# control-board-v1-fix.net
KiCad netlist of a schematic drawn in EAGLE
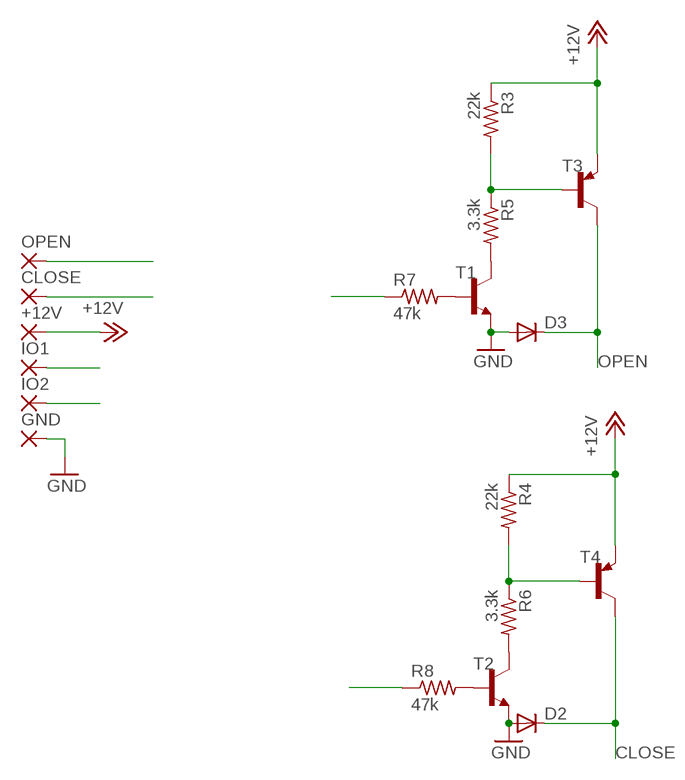
[diagram p0: schematic, sheet 1]

(export (version "E")
  (design (tool "Eeschema 10.0.6"))
  (components
    (comp (ref "+12V")
      (value "1,6/0,8")
      (footprint "eagle-import:1,6_0,8")
      (libsource (lib "eagle-import") (part "1,6/0,8"))
    )
    (comp (ref "CLOSE")
      (value "1,6/0,8")
      (footprint "eagle-import:1,6_0,8")
      (libsource (lib "eagle-import") (part "1,6/0,8"))
    )
    (comp (ref "D2")
      (value "DIODE-MICROMELF-W")
      (footprint "eagle-import:MICROMELF-W")
      (libsource (lib "eagle-import") (part "DIODE-MICROMELF-W"))
    )
    (comp (ref "D3")
      (value "DIODE-MICROMELF-W")
      (footprint "eagle-import:MICROMELF-W")
      (libsource (lib "eagle-import") (part "DIODE-MICROMELF-W"))
    )
    (comp (ref "GND")
      (value "1,6/0,8")
      (footprint "eagle-import:1,6_0,8")
      (libsource (lib "eagle-import") (part "1,6/0,8"))
    )
    (comp (ref "IO1")
      (value "1,6/0,8")
      (footprint "eagle-import:1,6_0,8")
      (libsource (lib "eagle-import") (part "1,6/0,8"))
    )
    (comp (ref "IO2")
      (value "1,6/0,8")
      (footprint "eagle-import:1,6_0,8")
      (libsource (lib "eagle-import") (part "1,6/0,8"))
    )
    (comp (ref "OPEN")
      (value "1,6/0,8")
      (footprint "eagle-import:1,6_0,8")
      (libsource (lib "eagle-import") (part "1,6/0,8"))
    )
    (comp (ref "R3")
      (value "22k")
      (footprint "eagle-import:R0603")
      (libsource (lib "eagle-import") (part "R-US_R0603"))
    )
    (comp (ref "R4")
      (value "22k")
      (footprint "eagle-import:R0603")
      (libsource (lib "eagle-import") (part "R-US_R0603"))
    )
    (comp (ref "R5")
      (value "3.3k")
      (footprint "eagle-import:R0603")
      (libsource (lib "eagle-import") (part "R-US_R0603"))
    )
    (comp (ref "R6")
      (value "3.3k")
      (footprint "eagle-import:R0603")
      (libsource (lib "eagle-import") (part "R-US_R0603"))
    )
    (comp (ref "R7")
      (value "47k")
      (footprint "eagle-import:R0603")
      (libsource (lib "eagle-import") (part "R-US_R0603"))
    )
    (comp (ref "R8")
      (value "47k")
      (footprint "eagle-import:R0603")
      (libsource (lib "eagle-import") (part "R-US_R0603"))
    )
    (comp (ref "T1")
      (value "BC808-NPN-SOT23-BEC")
      (footprint "eagle-import:SOT23-BEC")
      (libsource (lib "eagle-import") (part "-NPN-SOT23-BECBC808"))
    )
    (comp (ref "T2")
      (value "BC808-NPN-SOT23-BEC")
      (footprint "eagle-import:SOT23-BEC")
      (libsource (lib "eagle-import") (part "-NPN-SOT23-BECBC808"))
    )
    (comp (ref "T3")
      (value "BC807-16-PNP-SOT23-BEC")
      (footprint "eagle-import:SOT23-BEC")
      (libsource (lib "eagle-import") (part "-PNP-SOT23-BECBC807-16"))
    )
    (comp (ref "T4")
      (value "BC807-16-PNP-SOT23-BEC")
      (footprint "eagle-import:SOT23-BEC")
      (libsource (lib "eagle-import") (part "-PNP-SOT23-BECBC807-16"))
    )
  )
  (nets
    (net (code "1") (name "+12V") (class "Default")
      (node (ref "+12V") (pin "1") (pinfunction "P_1") (pintype "passive"))
      (node (ref "R3") (pin "1") (pinfunction "1_1") (pintype "passive"))
      (node (ref "R4") (pin "1") (pinfunction "1_1") (pintype "passive"))
      (node (ref "T3") (pin "E") (pinfunction "E_E") (pintype "passive"))
      (node (ref "T4") (pin "E") (pinfunction "E_E") (pintype "passive"))
    )
    (net (code "2") (name "/CLOSE") (class "Default")
      (node (ref "CLOSE") (pin "1") (pinfunction "P_1") (pintype "passive"))
      (node (ref "D2") (pin "C") (pinfunction "C_C") (pintype "passive"))
      (node (ref "T4") (pin "C") (pinfunction "C_C") (pintype "passive"))
    )
    (net (code "3") (name "/IO1") (class "Default")
      (node (ref "IO1") (pin "1") (pinfunction "P_1") (pintype "passive"))
      (node (ref "R7") (pin "1") (pinfunction "1_1") (pintype "passive"))
    )
    (net (code "4") (name "/IO2") (class "Default")
      (node (ref "IO2") (pin "1") (pinfunction "P_1") (pintype "passive"))
      (node (ref "R8") (pin "1") (pinfunction "1_1") (pintype "passive"))
    )
    (net (code "5") (name "/OPEN") (class "Default")
      (node (ref "D3") (pin "C") (pinfunction "C_C") (pintype "passive"))
      (node (ref "OPEN") (pin "1") (pinfunction "P_1") (pintype "passive"))
      (node (ref "T3") (pin "C") (pinfunction "C_C") (pintype "passive"))
    )
    (net (code "6") (name "GND") (class "Default")
      (node (ref "D2") (pin "A") (pinfunction "A_A") (pintype "passive"))
      (node (ref "D3") (pin "A") (pinfunction "A_A") (pintype "passive"))
      (node (ref "GND") (pin "1") (pinfunction "P_1") (pintype "passive"))
      (node (ref "T1") (pin "E") (pinfunction "E_E") (pintype "passive"))
      (node (ref "T2") (pin "E") (pinfunction "E_E") (pintype "passive"))
    )
    (net (code "7") (name "Net-(R3-Pad2)") (class "Default")
      (node (ref "R3") (pin "2") (pinfunction "2_2") (pintype "passive"))
      (node (ref "R5") (pin "1") (pinfunction "1_1") (pintype "passive"))
      (node (ref "T3") (pin "B") (pinfunction "B_B") (pintype "passive"))
    )
    (net (code "8") (name "Net-(R4-Pad2)") (class "Default")
      (node (ref "R4") (pin "2") (pinfunction "2_2") (pintype "passive"))
      (node (ref "R6") (pin "1") (pinfunction "1_1") (pintype "passive"))
      (node (ref "T4") (pin "B") (pinfunction "B_B") (pintype "passive"))
    )
    (net (code "9") (name "Net-(R5-Pad2)") (class "Default")
      (node (ref "R5") (pin "2") (pinfunction "2_2") (pintype "passive"))
      (node (ref "T1") (pin "C") (pinfunction "C_C") (pintype "passive"))
    )
    (net (code "10") (name "Net-(R6-Pad2)") (class "Default")
      (node (ref "R6") (pin "2") (pinfunction "2_2") (pintype "passive"))
      (node (ref "T2") (pin "C") (pinfunction "C_C") (pintype "passive"))
    )
    (net (code "11") (name "Net-(R7-Pad2)") (class "Default")
      (node (ref "R7") (pin "2") (pinfunction "2_2") (pintype "passive"))
      (node (ref "T1") (pin "B") (pinfunction "B_B") (pintype "passive"))
    )
    (net (code "12") (name "Net-(R8-Pad2)") (class "Default")
      (node (ref "R8") (pin "2") (pinfunction "2_2") (pintype "passive"))
      (node (ref "T2") (pin "B") (pinfunction "B_B") (pintype "passive"))
    )
  )
)
